# oscillateur.net
KiCad netlist of a schematic drawn in EAGLE
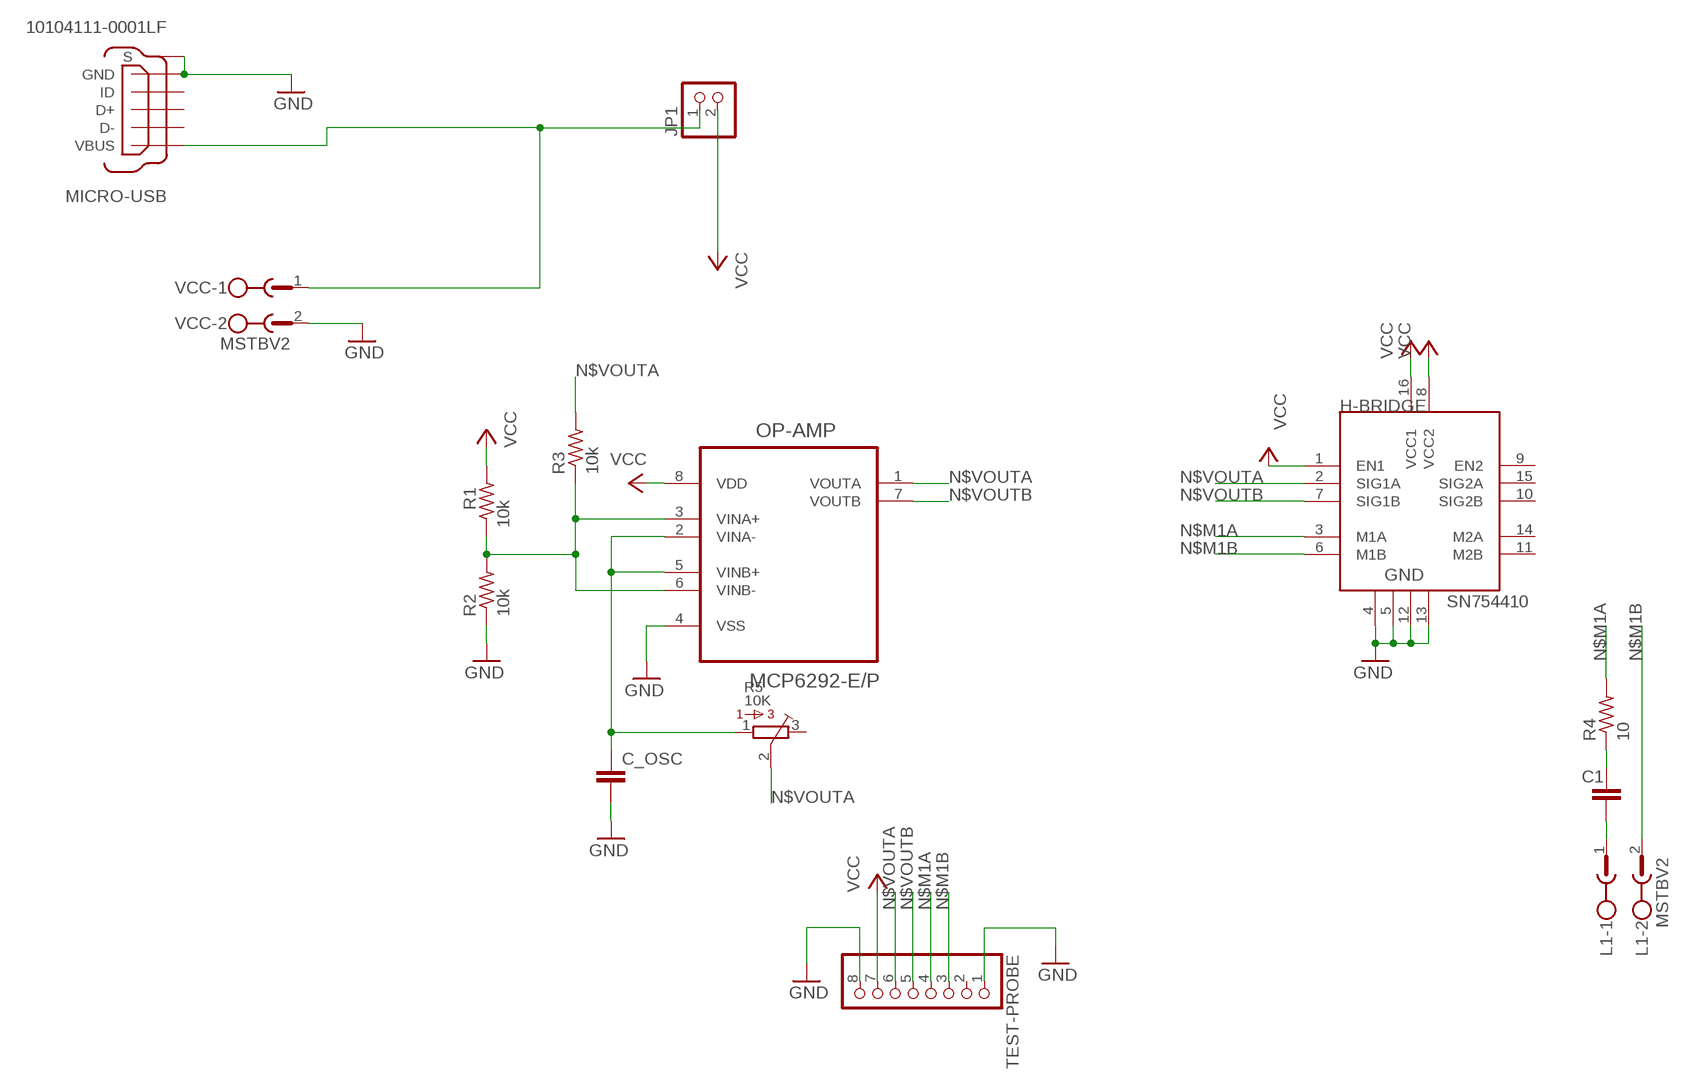
[diagram p0: schematic, sheet 1]

(export (version "E")
  (design (tool "Eeschema 10.0.6"))
  (components
    (comp (ref "C1")
      (value "C5/2.5")
      (footprint "eagle-import:C5B2.5")
      (libsource (lib "eagle-import") (part "C5/2.5"))
    )
    (comp (ref "C_OSC")
      (value "C5/2.5")
      (footprint "eagle-import:C5B2.5")
      (libsource (lib "eagle-import") (part "C5/2.5"))
    )
    (comp (ref "H-BRIDGE")
      (value "SN754410")
      (footprint "eagle-import:DIP16")
      (libsource (lib "eagle-import") (part "SN754410"))
    )
    (comp (ref "JP1")
      (value "PINHD-1X2")
      (footprint "eagle-import:1X02")
      (libsource (lib "eagle-import") (part "PINHD-1X2"))
    )
    (comp (ref "L1")
      (value "MSTBV2")
      (footprint "eagle-import:MSTBV2")
      (fields (field (name "MPN") "MSTBV 2,5/2-GF-5.08"))
      (libsource (lib "eagle-import") (part "MSTBV2"))
    )
    (comp (ref "MICRO-USB")
      (value "10104111-0001LF")
      (footprint "eagle-import:FRAMATOME_10104111-0001LF")
      (fields (field (name "MF") "Amphenol ICC"))
      (libsource (lib "eagle-import") (part "10104111-0001LF"))
    )
    (comp (ref "OP-AMP")
      (value "MCP6292-E/P")
      (footprint "eagle-import:DIP254P762X432-8")
      (fields (field (name "MF") "Microchip"))
      (libsource (lib "eagle-import") (part "MCP6292-E/P"))
    )
    (comp (ref "R1")
      (value "10k")
      (footprint "eagle-import:0207_10")
      (libsource (lib "eagle-import") (part "R-US_0207/10"))
    )
    (comp (ref "R2")
      (value "10k")
      (footprint "eagle-import:0207_10")
      (libsource (lib "eagle-import") (part "R-US_0207/10"))
    )
    (comp (ref "R3")
      (value "10k")
      (footprint "eagle-import:0207_10")
      (libsource (lib "eagle-import") (part "R-US_0207/10"))
    )
    (comp (ref "R4")
      (value "10")
      (footprint "eagle-import:0207_10")
      (libsource (lib "eagle-import") (part "R-US_0207/10"))
    )
    (comp (ref "R5")
      (value "10K")
      (footprint "eagle-import:3362R")
      (libsource (lib "eagle-import") (part "3362R"))
    )
    (comp (ref "TEST-PROBE")
      (value "PINHD-1X8")
      (footprint "eagle-import:1X08")
      (libsource (lib "eagle-import") (part "PINHD-1X8"))
    )
    (comp (ref "VCC")
      (value "MSTBV2")
      (footprint "eagle-import:MSTBV2")
      (fields (field (name "MPN") "MSTBV 2,5/2-GF-5.08"))
      (libsource (lib "eagle-import") (part "MSTBV2"))
    )
  )
  (nets
    (net (code "1") (name "/N$M1A") (class "Default")
      (node (ref "H-BRIDGE") (pin "3") (pinfunction "M1A_3") (pintype "bidirectional"))
      (node (ref "R4") (pin "2") (pinfunction "2_2") (pintype "passive"))
      (node (ref "TEST-PROBE") (pin "4") (pinfunction "4_4") (pintype "passive"))
    )
    (net (code "2") (name "/N$M1B") (class "Default")
      (node (ref "H-BRIDGE") (pin "6") (pinfunction "M1B_6") (pintype "bidirectional"))
      (node (ref "L1") (pin "2") (pinfunction "1_2") (pintype "passive"))
      (node (ref "TEST-PROBE") (pin "3") (pinfunction "3_3") (pintype "passive"))
    )
    (net (code "3") (name "/N$VOUTA") (class "Default")
      (node (ref "H-BRIDGE") (pin "2") (pinfunction "SIG1A_2") (pintype "bidirectional"))
      (node (ref "OP-AMP") (pin "1") (pinfunction "VOUTA_1") (pintype "output"))
      (node (ref "R3") (pin "2") (pinfunction "2_2") (pintype "passive"))
      (node (ref "R5") (pin "2") (pinfunction "2_2") (pintype "passive"))
      (node (ref "TEST-PROBE") (pin "6") (pinfunction "6_6") (pintype "passive"))
    )
    (net (code "4") (name "/N$VOUTB") (class "Default")
      (node (ref "H-BRIDGE") (pin "7") (pinfunction "SIG1B_7") (pintype "bidirectional"))
      (node (ref "OP-AMP") (pin "7") (pinfunction "VOUTB_7") (pintype "output"))
      (node (ref "TEST-PROBE") (pin "5") (pinfunction "5_5") (pintype "passive"))
    )
    (net (code "5") (name "GND") (class "Default")
      (node (ref "C_OSC") (pin "2") (pinfunction "2_2") (pintype "passive"))
      (node (ref "H-BRIDGE") (pin "12") (pinfunction "P12_12") (pintype "power_in"))
      (node (ref "H-BRIDGE") (pin "13") (pinfunction "P13_13") (pintype "power_in"))
      (node (ref "H-BRIDGE") (pin "4") (pinfunction "P4_4") (pintype "power_in"))
      (node (ref "H-BRIDGE") (pin "5") (pinfunction "P5_5") (pintype "power_in"))
      (node (ref "MICRO-USB") (pin "5") (pinfunction "GND_5") (pintype "power_in"))
      (node (ref "MICRO-USB") (pin "6") (pinfunction "S_6") (pintype "power_in"))
      (node (ref "MICRO-USB") (pin "7") (pinfunction "S_7") (pintype "power_in"))
      (node (ref "MICRO-USB") (pin "8") (pinfunction "S_8") (pintype "power_in"))
      (node (ref "MICRO-USB") (pin "9") (pinfunction "S_9") (pintype "power_in"))
      (node (ref "OP-AMP") (pin "4") (pinfunction "VSS_4") (pintype "power_in"))
      (node (ref "R2") (pin "1") (pinfunction "1_1") (pintype "passive"))
      (node (ref "TEST-PROBE") (pin "1") (pinfunction "1_1") (pintype "passive"))
      (node (ref "TEST-PROBE") (pin "8") (pinfunction "8_8") (pintype "passive"))
      (node (ref "VCC") (pin "2") (pinfunction "1_2") (pintype "passive"))
    )
    (net (code "6") (name "Net-(C1-Pad1)") (class "Default")
      (node (ref "C1") (pin "1") (pinfunction "1_1") (pintype "passive"))
      (node (ref "R4") (pin "1") (pinfunction "1_1") (pintype "passive"))
    )
    (net (code "7") (name "Net-(C1-Pad2)") (class "Default")
      (node (ref "C1") (pin "2") (pinfunction "2_2") (pintype "passive"))
      (node (ref "L1") (pin "1") (pinfunction "1_1") (pintype "passive"))
    )
    (net (code "8") (name "Net-(MICRO-USB-VBUS)") (class "Default")
      (node (ref "JP1") (pin "1") (pinfunction "1_1") (pintype "passive"))
      (node (ref "MICRO-USB") (pin "1") (pinfunction "VBUS_1") (pintype "power_in"))
      (node (ref "VCC") (pin "1") (pinfunction "1_1") (pintype "passive"))
    )
    (net (code "9") (name "Net-(OP-AMP-VINA+)") (class "Default")
      (node (ref "OP-AMP") (pin "3") (pinfunction "VINA+_3") (pintype "input"))
      (node (ref "OP-AMP") (pin "6") (pinfunction "VINB-_6") (pintype "input"))
      (node (ref "R1") (pin "1") (pinfunction "1_1") (pintype "passive"))
      (node (ref "R2") (pin "2") (pinfunction "2_2") (pintype "passive"))
      (node (ref "R3") (pin "1") (pinfunction "1_1") (pintype "passive"))
    )
    (net (code "10") (name "Net-(OP-AMP-VINA-)") (class "Default")
      (node (ref "C_OSC") (pin "1") (pinfunction "1_1") (pintype "passive"))
      (node (ref "OP-AMP") (pin "2") (pinfunction "VINA-_2") (pintype "input"))
      (node (ref "OP-AMP") (pin "5") (pinfunction "VINB+_5") (pintype "input"))
      (node (ref "R5") (pin "1") (pinfunction "1_1") (pintype "passive"))
    )
    (net (code "11") (name "VCC") (class "Default")
      (node (ref "H-BRIDGE") (pin "1") (pinfunction "EN1_1") (pintype "bidirectional"))
      (node (ref "H-BRIDGE") (pin "16") (pinfunction "VCC1_16") (pintype "power_in"))
      (node (ref "H-BRIDGE") (pin "8") (pinfunction "VCC2_8") (pintype "power_in"))
      (node (ref "JP1") (pin "2") (pinfunction "2_2") (pintype "passive"))
      (node (ref "OP-AMP") (pin "8") (pinfunction "VDD_8") (pintype "power_in"))
      (node (ref "R1") (pin "2") (pinfunction "2_2") (pintype "passive"))
      (node (ref "TEST-PROBE") (pin "7") (pinfunction "7_7") (pintype "passive"))
    )
    (net (code "12") (name "unconnected-(H-BRIDGE-EN2-Pad9)") (class "Default")
      (node (ref "H-BRIDGE") (pin "9") (pinfunction "EN2_9") (pintype "bidirectional"))
    )
    (net (code "13") (name "unconnected-(H-BRIDGE-M2A-Pad14)") (class "Default")
      (node (ref "H-BRIDGE") (pin "14") (pinfunction "M2A_14") (pintype "bidirectional"))
    )
    (net (code "14") (name "unconnected-(H-BRIDGE-M2B-Pad11)") (class "Default")
      (node (ref "H-BRIDGE") (pin "11") (pinfunction "M2B_11") (pintype "bidirectional"))
    )
    (net (code "15") (name "unconnected-(H-BRIDGE-SIG2A-Pad15)") (class "Default")
      (node (ref "H-BRIDGE") (pin "15") (pinfunction "SIG2A_15") (pintype "bidirectional"))
    )
    (net (code "16") (name "unconnected-(H-BRIDGE-SIG2B-Pad10)") (class "Default")
      (node (ref "H-BRIDGE") (pin "10") (pinfunction "SIG2B_10") (pintype "bidirectional"))
    )
    (net (code "17") (name "unconnected-(MICRO-USB-D+-Pad3)") (class "Default")
      (node (ref "MICRO-USB") (pin "3") (pinfunction "D+_3") (pintype "passive"))
    )
    (net (code "18") (name "unconnected-(MICRO-USB-D--Pad2)") (class "Default")
      (node (ref "MICRO-USB") (pin "2") (pinfunction "D-_2") (pintype "passive"))
    )
    (net (code "19") (name "unconnected-(MICRO-USB-ID-Pad4)") (class "Default")
      (node (ref "MICRO-USB") (pin "4") (pinfunction "ID_4") (pintype "passive"))
    )
    (net (code "20") (name "unconnected-(R5-Pad3)") (class "Default")
      (node (ref "R5") (pin "3") (pinfunction "3_3") (pintype "passive"))
    )
    (net (code "21") (name "unconnected-(TEST-PROBE-Pad2)") (class "Default")
      (node (ref "TEST-PROBE") (pin "2") (pinfunction "2_2") (pintype "passive"))
    )
  )
)
